# candle-001.net
KiCad netlist of a schematic drawn in EAGLE
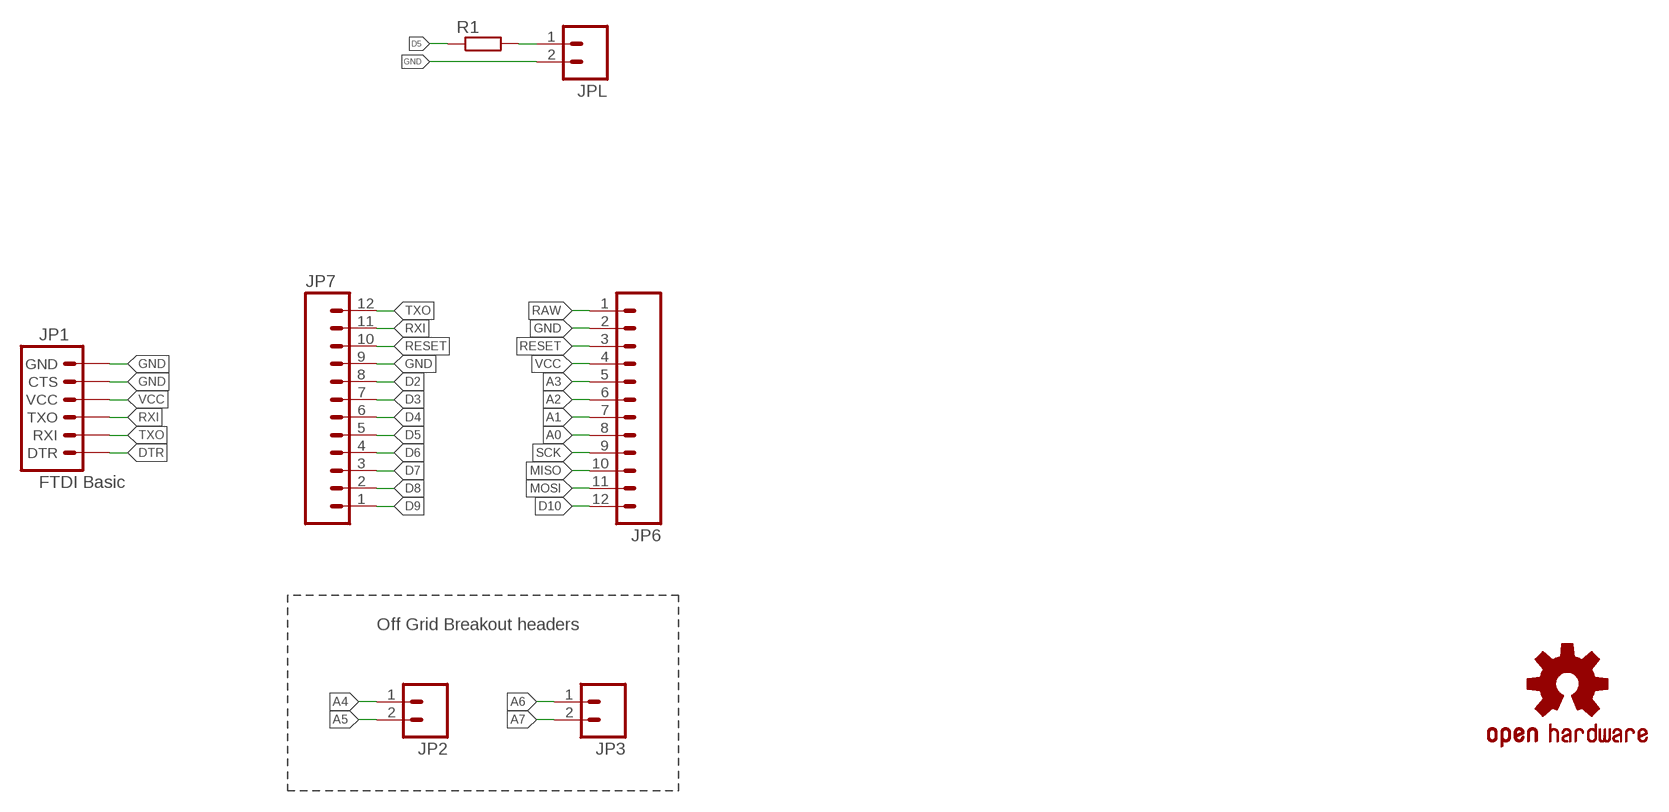
[diagram p0: schematic, sheet 1]

(export (version "E")
  (design (tool "Eeschema 10.0.6"))
  (components
    (comp (ref "JP1")
      (value "FTDI Basic")
      (footprint "eagle-import:1X06")
      (libsource (lib "eagle-import") (part "ARDUINO_SERIAL_PROGRAMPTH"))
    )
    (comp (ref "JP2")
      (value "M02PTH")
      (footprint "eagle-import:1X02")
      (libsource (lib "eagle-import") (part "M02PTH"))
    )
    (comp (ref "JP3")
      (value "M02PTH")
      (footprint "eagle-import:1X02")
      (libsource (lib "eagle-import") (part "M02PTH"))
    )
    (comp (ref "JP6")
      (value "M12PTH")
      (footprint "eagle-import:1X12")
      (libsource (lib "eagle-import") (part "M12PTH"))
    )
    (comp (ref "JP7")
      (value "M12PTH")
      (footprint "eagle-import:1X12")
      (libsource (lib "eagle-import") (part "M12PTH"))
    )
    (comp (ref "JPL")
      (value "M02PTH")
      (footprint "eagle-import:1X02")
      (libsource (lib "eagle-import") (part "M02PTH"))
    )
    (comp (ref "R1")
      (value "R-EU_0204/5")
      (footprint "eagle-import:0204_5")
      (libsource (lib "eagle-import") (part "R-EU_0204/5"))
    )
    (comp (ref "U$3")
      (value "OSHW-LOGOS")
      (footprint "eagle-import:OSHW-LOGO-S")
      (libsource (lib "eagle-import") (part "OSHW-LOGOS"))
    )
  )
  (nets
    (net (code "1") (name "A0") (class "Default")
      (node (ref "JP6") (pin "8") (pinfunction "8_8") (pintype "passive"))
    )
    (net (code "2") (name "A1") (class "Default")
      (node (ref "JP6") (pin "7") (pinfunction "7_7") (pintype "passive"))
    )
    (net (code "3") (name "A2") (class "Default")
      (node (ref "JP6") (pin "6") (pinfunction "6_6") (pintype "passive"))
    )
    (net (code "4") (name "A3") (class "Default")
      (node (ref "JP6") (pin "5") (pinfunction "5_5") (pintype "passive"))
    )
    (net (code "5") (name "A4") (class "Default")
      (node (ref "JP2") (pin "1") (pinfunction "1_1") (pintype "passive"))
    )
    (net (code "6") (name "A5") (class "Default")
      (node (ref "JP2") (pin "2") (pinfunction "2_2") (pintype "passive"))
    )
    (net (code "7") (name "A6") (class "Default")
      (node (ref "JP3") (pin "1") (pinfunction "1_1") (pintype "passive"))
    )
    (net (code "8") (name "A7") (class "Default")
      (node (ref "JP3") (pin "2") (pinfunction "2_2") (pintype "passive"))
    )
    (net (code "9") (name "D2") (class "Default")
      (node (ref "JP7") (pin "8") (pinfunction "8_8") (pintype "passive"))
    )
    (net (code "10") (name "D3") (class "Default")
      (node (ref "JP7") (pin "7") (pinfunction "7_7") (pintype "passive"))
    )
    (net (code "11") (name "D4") (class "Default")
      (node (ref "JP7") (pin "6") (pinfunction "6_6") (pintype "passive"))
    )
    (net (code "12") (name "D5") (class "Default")
      (node (ref "JP7") (pin "5") (pinfunction "5_5") (pintype "passive"))
      (node (ref "R1") (pin "1") (pinfunction "1_1") (pintype "passive"))
    )
    (net (code "13") (name "D6") (class "Default")
      (node (ref "JP7") (pin "4") (pinfunction "4_4") (pintype "passive"))
    )
    (net (code "14") (name "D7") (class "Default")
      (node (ref "JP7") (pin "3") (pinfunction "3_3") (pintype "passive"))
    )
    (net (code "15") (name "D8") (class "Default")
      (node (ref "JP7") (pin "2") (pinfunction "2_2") (pintype "passive"))
    )
    (net (code "16") (name "D9") (class "Default")
      (node (ref "JP7") (pin "1") (pinfunction "1_1") (pintype "passive"))
    )
    (net (code "17") (name "D10") (class "Default")
      (node (ref "JP6") (pin "12") (pinfunction "12_12") (pintype "passive"))
    )
    (net (code "18") (name "DTR") (class "Default")
      (node (ref "JP1") (pin "1") (pinfunction "DTR_1") (pintype "passive"))
    )
    (net (code "19") (name "GND") (class "Default")
      (node (ref "JP1") (pin "5") (pinfunction "CTS_5") (pintype "passive"))
      (node (ref "JP1") (pin "6") (pinfunction "GND_6") (pintype "passive"))
      (node (ref "JP6") (pin "2") (pinfunction "2_2") (pintype "passive"))
      (node (ref "JP7") (pin "9") (pinfunction "9_9") (pintype "passive"))
      (node (ref "JPL") (pin "2") (pinfunction "2_2") (pintype "passive"))
    )
    (net (code "20") (name "MISO") (class "Default")
      (node (ref "JP6") (pin "10") (pinfunction "10_10") (pintype "passive"))
    )
    (net (code "21") (name "MOSI") (class "Default")
      (node (ref "JP6") (pin "11") (pinfunction "11_11") (pintype "passive"))
    )
    (net (code "22") (name "Net-(JPL-Pad1)") (class "Default")
      (node (ref "JPL") (pin "1") (pinfunction "1_1") (pintype "passive"))
      (node (ref "R1") (pin "2") (pinfunction "2_2") (pintype "passive"))
    )
    (net (code "23") (name "RAW") (class "Default")
      (node (ref "JP6") (pin "1") (pinfunction "1_1") (pintype "passive"))
    )
    (net (code "24") (name "RESET") (class "Default")
      (node (ref "JP6") (pin "3") (pinfunction "3_3") (pintype "passive"))
      (node (ref "JP7") (pin "10") (pinfunction "10_10") (pintype "passive"))
    )
    (net (code "25") (name "RXI") (class "Default")
      (node (ref "JP1") (pin "3") (pinfunction "TXO_3") (pintype "passive"))
      (node (ref "JP7") (pin "11") (pinfunction "11_11") (pintype "passive"))
    )
    (net (code "26") (name "SCK") (class "Default")
      (node (ref "JP6") (pin "9") (pinfunction "9_9") (pintype "passive"))
    )
    (net (code "27") (name "TXO") (class "Default")
      (node (ref "JP1") (pin "2") (pinfunction "RXI_2") (pintype "passive"))
      (node (ref "JP7") (pin "12") (pinfunction "12_12") (pintype "passive"))
    )
    (net (code "28") (name "VCC") (class "Default")
      (node (ref "JP1") (pin "4") (pinfunction "VCC_4") (pintype "passive"))
      (node (ref "JP6") (pin "4") (pinfunction "4_4") (pintype "passive"))
    )
  )
)
